# FPGA_GTP.net
KiCad netlist of a schematic drawn in Altium Designer
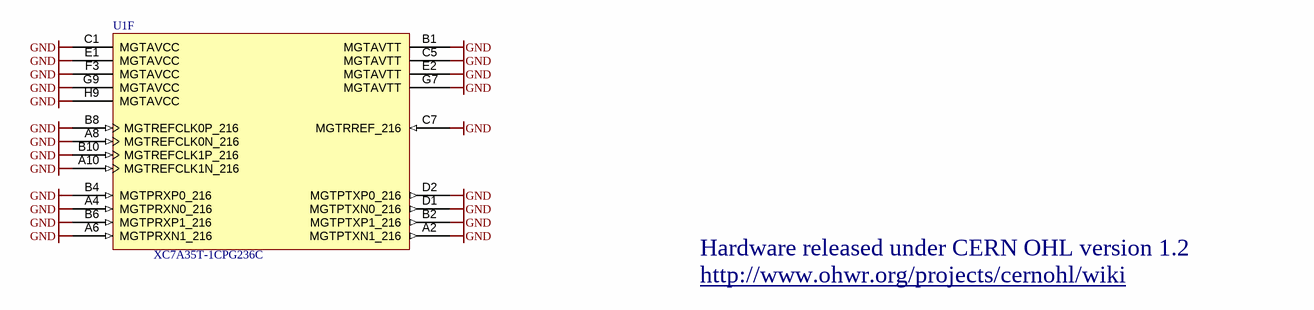
[diagram p0: FPGA_GTP.SchDoc]

(export (version "E")
  (design (tool "Eeschema 10.0.6"))
  (components
    (comp (ref "U1")
      (value "XC7A35T-1CPG236C")
      (footprint "XC7AxxT-CPG236")
      (libsource (lib "TE") (part "XC7A35T-CPG236"))
    )
  )
  (nets
    (net (code "1") (name "GND") (class "Default")
      (node (ref "U1") (pin "A10") (pinfunction "MGTREFCLK1N_216_A10") (pintype "input"))
      (node (ref "U1") (pin "A2") (pinfunction "MGTPTXN1_216_A2") (pintype "output"))
      (node (ref "U1") (pin "A4") (pinfunction "MGTPRXN0_216_A4") (pintype "input"))
      (node (ref "U1") (pin "A6") (pinfunction "MGTPRXN1_216_A6") (pintype "input"))
      (node (ref "U1") (pin "A8") (pinfunction "MGTREFCLK0N_216_A8") (pintype "input"))
      (node (ref "U1") (pin "B1") (pinfunction "MGTAVTT_B1") (pintype "power_in"))
      (node (ref "U1") (pin "B10") (pinfunction "MGTREFCLK1P_216_B10") (pintype "input"))
      (node (ref "U1") (pin "B2") (pinfunction "MGTPTXP1_216_B2") (pintype "output"))
      (node (ref "U1") (pin "B4") (pinfunction "MGTPRXP0_216_B4") (pintype "input"))
      (node (ref "U1") (pin "B6") (pinfunction "MGTPRXP1_216_B6") (pintype "input"))
      (node (ref "U1") (pin "B8") (pinfunction "MGTREFCLK0P_216_B8") (pintype "input"))
      (node (ref "U1") (pin "C1") (pinfunction "MGTAVCC_C1") (pintype "power_in"))
      (node (ref "U1") (pin "C5") (pinfunction "MGTAVTT_C5") (pintype "power_in"))
      (node (ref "U1") (pin "C7") (pinfunction "MGTRREF_216_C7") (pintype "input"))
      (node (ref "U1") (pin "D1") (pinfunction "MGTPTXN0_216_D1") (pintype "output"))
      (node (ref "U1") (pin "D2") (pinfunction "MGTPTXP0_216_D2") (pintype "output"))
      (node (ref "U1") (pin "E1") (pinfunction "MGTAVCC_E1") (pintype "power_in"))
      (node (ref "U1") (pin "E2") (pinfunction "MGTAVTT_E2") (pintype "power_in"))
      (node (ref "U1") (pin "F3") (pinfunction "MGTAVCC_F3") (pintype "power_in"))
      (node (ref "U1") (pin "G7") (pinfunction "MGTAVTT_G7") (pintype "power_in"))
      (node (ref "U1") (pin "G9") (pinfunction "MGTAVCC_G9") (pintype "power_in"))
      (node (ref "U1") (pin "H9") (pinfunction "MGTAVCC_H9") (pintype "power_in"))
    )
  )
)
